# SECDONGL_001.net
KiCad netlist of a schematic drawn in EAGLE
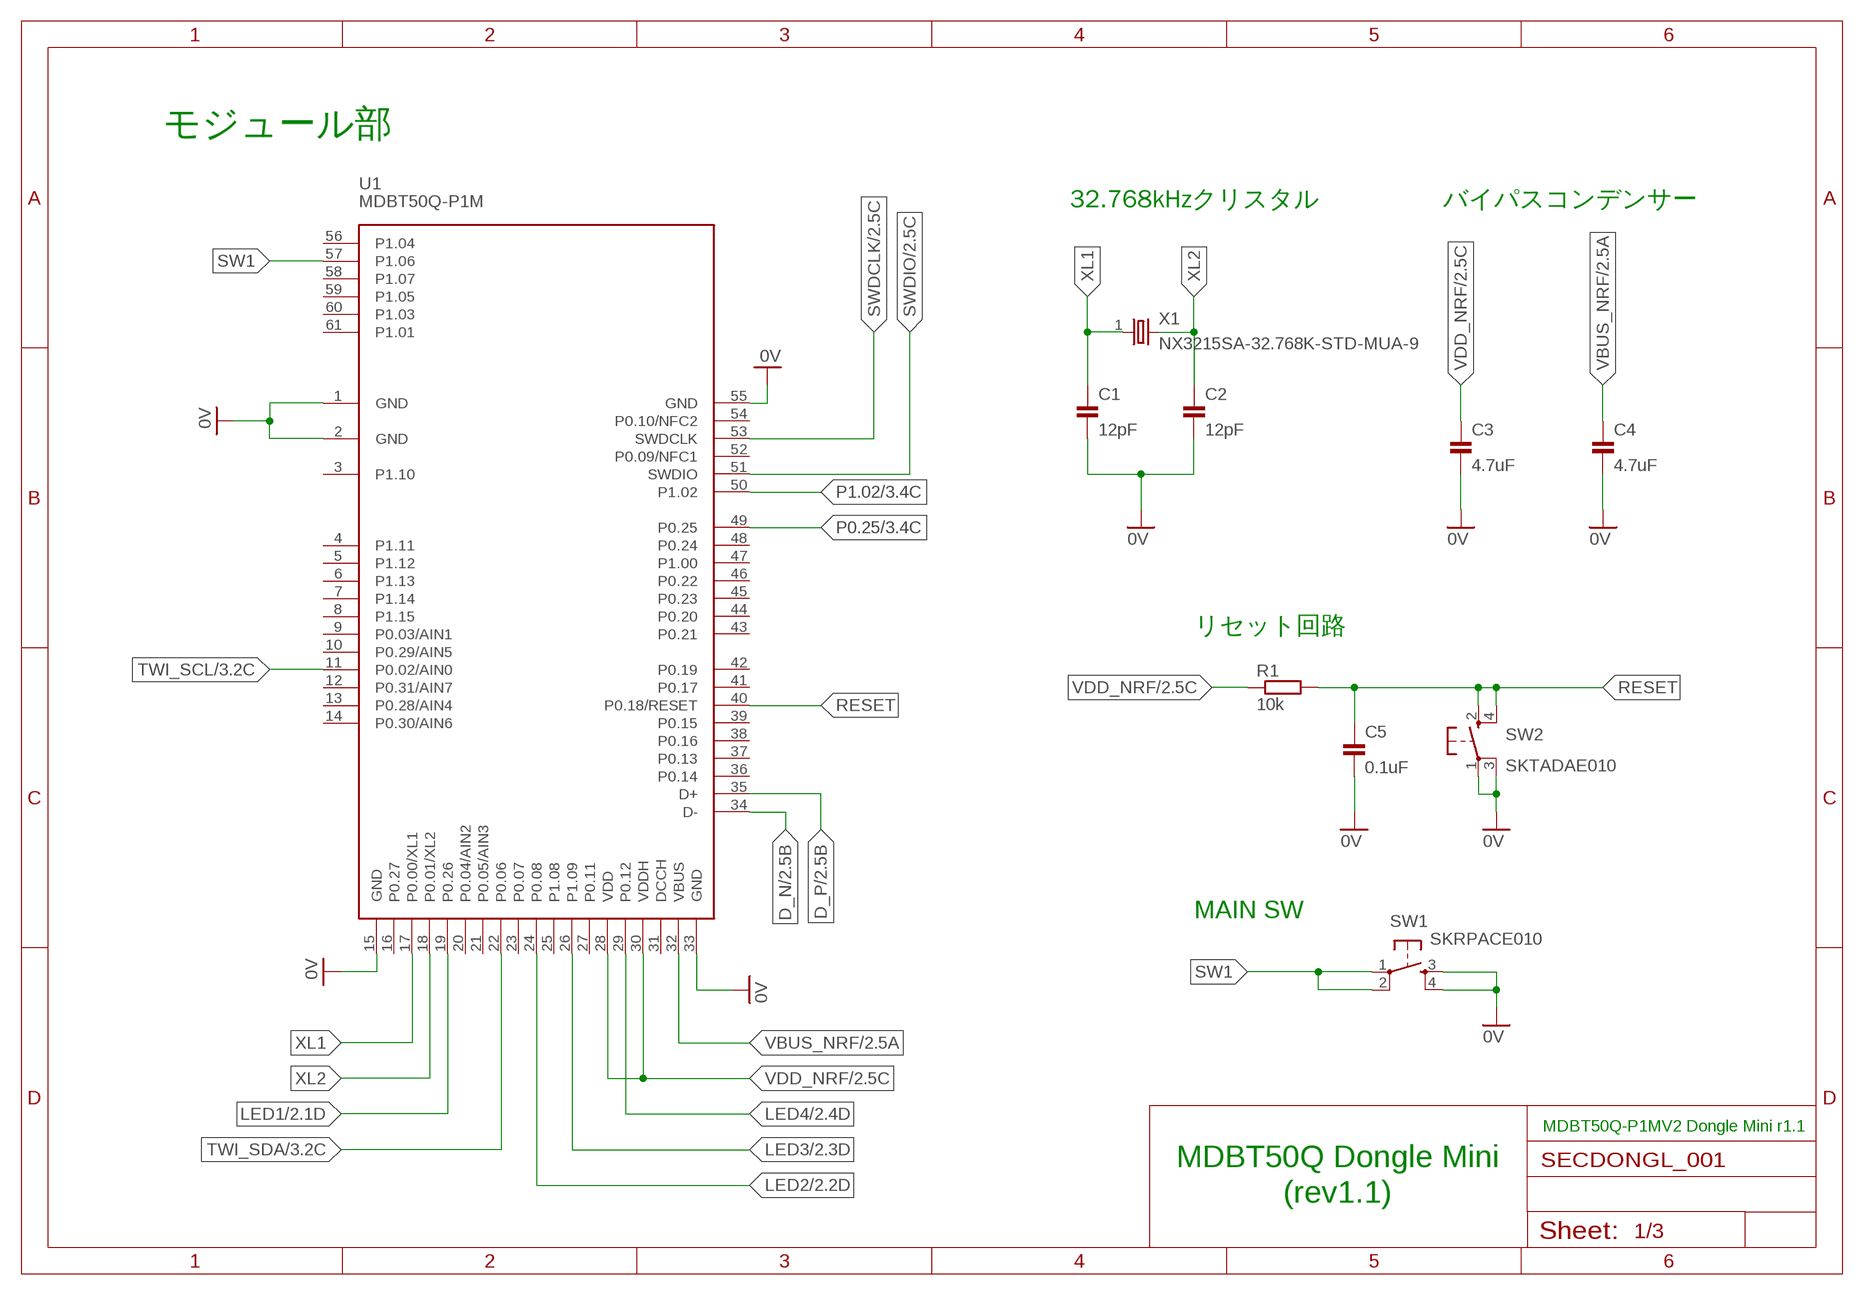
[diagram p0: schematic, sheet 1]
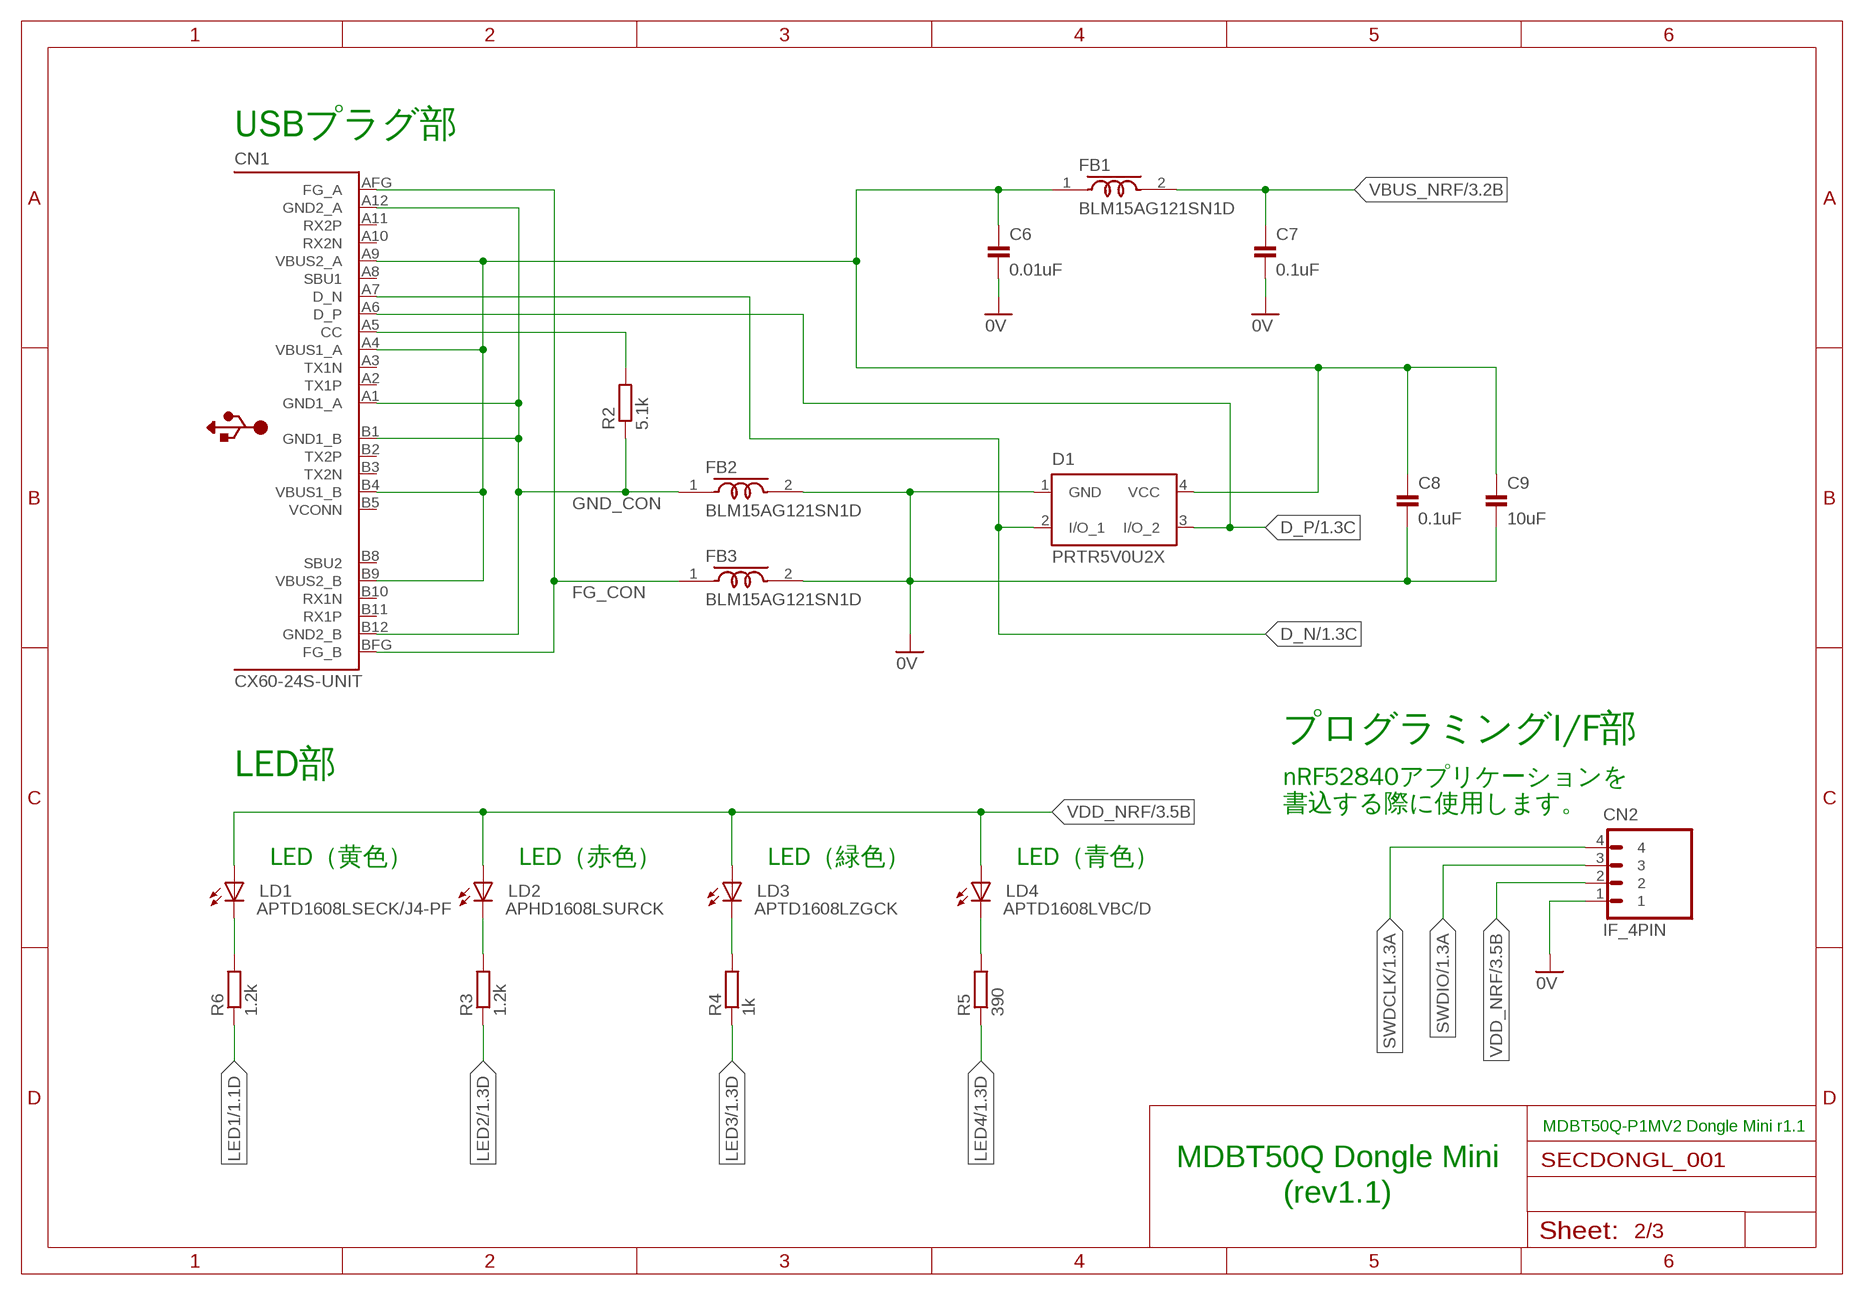
[diagram p1: schematic, sheet 2]
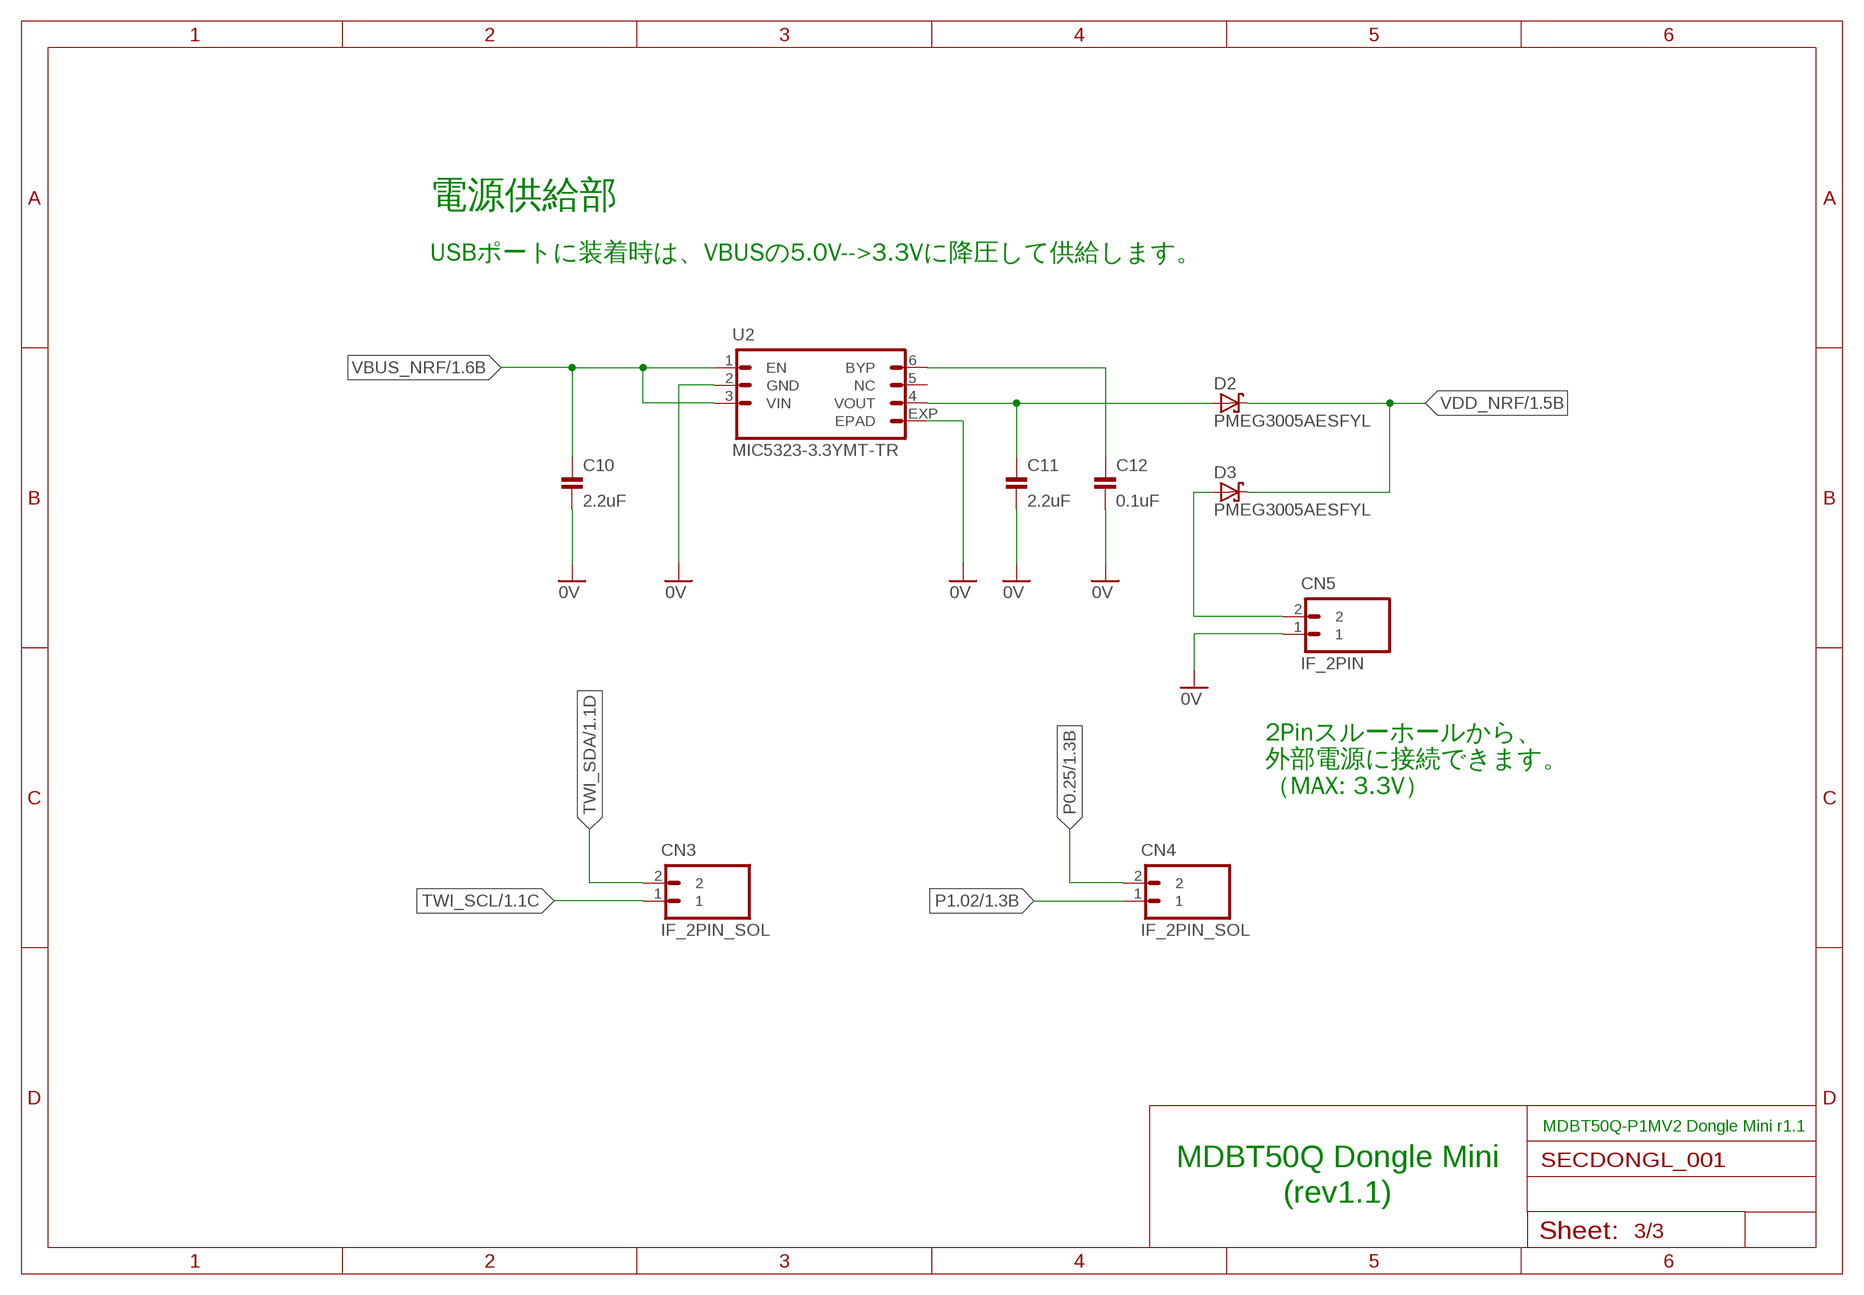
[diagram p2: schematic, sheet 3]

(export (version "E")
  (design (tool "Eeschema 10.0.6"))
  (components
    (comp (ref "C6")
      (value "0.01uF")
      (footprint "eagle-import:C0402K")
      (libsource (lib "eagle-import") (part "CAP_0402K"))
    )
    (comp (ref "C7")
      (value "0.1uF")
      (footprint "eagle-import:C0402K")
      (libsource (lib "eagle-import") (part "CAP_0402K"))
    )
    (comp (ref "C8")
      (value "0.1uF")
      (footprint "eagle-import:C0402K")
      (libsource (lib "eagle-import") (part "CAP_0402K"))
    )
    (comp (ref "C9")
      (value "10uF")
      (footprint "eagle-import:C0603K")
      (libsource (lib "eagle-import") (part "CAP_0603"))
    )
    (comp (ref "CN1")
      (value "CX60-24S-UNIT")
      (footprint "eagle-import:CX60-24S-UNIT")
      (libsource (lib "eagle-import") (part "CX60-24S-UNIT"))
    )
    (comp (ref "CN2")
      (value "IF_4PIN")
      (footprint "eagle-import:HEADER_4PIN")
      (libsource (lib "eagle-import") (part "IF_4PIN"))
    )
    (comp (ref "D1")
      (value "PRTR5V0U2X")
      (footprint "eagle-import:SOT143B")
      (libsource (lib "eagle-import") (part "PRTR5V0U2X"))
    )
    (comp (ref "FB1")
      (value "BLM15AG121SN1D")
      (footprint "eagle-import:C0402K")
      (libsource (lib "eagle-import") (part "BLM15AG121SN1D"))
    )
    (comp (ref "FB2")
      (value "BLM15AG121SN1D")
      (footprint "eagle-import:C0402K")
      (libsource (lib "eagle-import") (part "BLM15AG121SN1D"))
    )
    (comp (ref "FB3")
      (value "BLM15AG121SN1D")
      (footprint "eagle-import:C0402K")
      (libsource (lib "eagle-import") (part "BLM15AG121SN1D"))
    )
    (comp (ref "LD1")
      (value "APTD1608LSECK/J4-PF")
      (footprint "eagle-import:APTD1608")
      (libsource (lib "eagle-import") (part "APTD1608LSECK/J4-PF"))
    )
    (comp (ref "LD2")
      (value "APHD1608LSURCK")
      (footprint "eagle-import:APTD1608")
      (libsource (lib "eagle-import") (part "APHD1608LSURCK"))
    )
    (comp (ref "LD3")
      (value "APTD1608LZGCK")
      (footprint "eagle-import:APTD1608")
      (libsource (lib "eagle-import") (part "APTD1608LZGCK"))
    )
    (comp (ref "LD4")
      (value "APTD1608LVBC/D")
      (footprint "eagle-import:APTD1608")
      (libsource (lib "eagle-import") (part "APTD1608LVBC/D"))
    )
    (comp (ref "R2")
      (value "5.1k")
      (footprint "eagle-import:R0402")
      (libsource (lib "eagle-import") (part "RESISTOR_0402"))
    )
    (comp (ref "R3")
      (value "1.2k")
      (footprint "eagle-import:R0402")
      (libsource (lib "eagle-import") (part "RESISTOR_0402"))
    )
    (comp (ref "R4")
      (value "1k")
      (footprint "eagle-import:R0402")
      (libsource (lib "eagle-import") (part "RESISTOR_0402"))
    )
    (comp (ref "R5")
      (value "390")
      (footprint "eagle-import:R0402")
      (libsource (lib "eagle-import") (part "RESISTOR_0402"))
    )
    (comp (ref "R6")
      (value "1.2k")
      (footprint "eagle-import:R0402")
      (libsource (lib "eagle-import") (part "RESISTOR_0402"))
    )
    (comp (ref "C1")
      (value "12pF")
      (footprint "eagle-import:C0603K")
      (libsource (lib "eagle-import") (part "CAP_0603"))
    )
    (comp (ref "C2")
      (value "12pF")
      (footprint "eagle-import:C0603K")
      (libsource (lib "eagle-import") (part "CAP_0603"))
    )
    (comp (ref "C3")
      (value "4.7uF")
      (footprint "eagle-import:C0603K")
      (libsource (lib "eagle-import") (part "CAP_0603"))
    )
    (comp (ref "C4")
      (value "4.7uF")
      (footprint "eagle-import:C0603K")
      (libsource (lib "eagle-import") (part "CAP_0603"))
    )
    (comp (ref "C5")
      (value "0.1uF")
      (footprint "eagle-import:C0402K")
      (libsource (lib "eagle-import") (part "CAP_0402K"))
    )
    (comp (ref "R1")
      (value "10k")
      (footprint "eagle-import:R0402")
      (libsource (lib "eagle-import") (part "RESISTOR_0402"))
    )
    (comp (ref "SW1")
      (value "SKRPACE010")
      (footprint "eagle-import:SKRPACE010")
      (libsource (lib "eagle-import") (part "SKRPACE010"))
    )
    (comp (ref "SW2")
      (value "SKTADAE010")
      (footprint "eagle-import:SKTADAE010")
      (libsource (lib "eagle-import") (part "SKTADAE010"))
    )
    (comp (ref "U1")
      (value "MDBT50Q-P1M")
      (footprint "eagle-import:MDBT50Q-P1M")
      (libsource (lib "eagle-import") (part "MDBT50Q-P1M"))
    )
    (comp (ref "X1")
      (value "NX3215SA-32.768K-STD-MUA-9")
      (footprint "eagle-import:NX3215")
      (libsource (lib "eagle-import") (part "NX3215SA-32.768K-STD-MUA-9"))
    )
    (comp (ref "C10")
      (value "2.2uF")
      (footprint "eagle-import:C0603K")
      (libsource (lib "eagle-import") (part "CAP_0603"))
    )
    (comp (ref "C11")
      (value "2.2uF")
      (footprint "eagle-import:C0603K")
      (libsource (lib "eagle-import") (part "CAP_0603"))
    )
    (comp (ref "C12")
      (value "0.1uF")
      (footprint "eagle-import:C0402K")
      (libsource (lib "eagle-import") (part "CAP_0402K"))
    )
    (comp (ref "CN3")
      (value "IF_2PIN_SOL")
      (footprint "eagle-import:SOLPAD_2PIN")
      (libsource (lib "eagle-import") (part "IF_2PIN_SOL"))
    )
    (comp (ref "CN4")
      (value "IF_2PIN_SOL")
      (footprint "eagle-import:SOLPAD_2PIN")
      (libsource (lib "eagle-import") (part "IF_2PIN_SOL"))
    )
    (comp (ref "CN5")
      (value "IF_2PIN")
      (footprint "eagle-import:HEADER_2P")
      (libsource (lib "eagle-import") (part "IF_2PIN"))
    )
    (comp (ref "D2")
      (value "PMEG3005AESFYL")
      (footprint "eagle-import:SOD962-2")
      (libsource (lib "eagle-import") (part "PMEG3005AESFYL"))
    )
    (comp (ref "D3")
      (value "PMEG3005AESFYL")
      (footprint "eagle-import:SOD962-2")
      (libsource (lib "eagle-import") (part "PMEG3005AESFYL"))
    )
    (comp (ref "U2")
      (value "MIC5323-3.3YMT-TR")
      (footprint "eagle-import:6-VDFN(2X2)")
      (libsource (lib "eagle-import") (part "MIC5323-3.3YMT-TR"))
    )
  )
  (nets
    (net (code "1") (name "0V") (class "Default")
      (node (ref "C1") (pin "2") (pinfunction "2_2") (pintype "passive"))
      (node (ref "C10") (pin "2") (pinfunction "2_2") (pintype "passive"))
      (node (ref "C11") (pin "2") (pinfunction "2_2") (pintype "passive"))
      (node (ref "C12") (pin "2") (pinfunction "2_2") (pintype "passive"))
      (node (ref "C2") (pin "2") (pinfunction "2_2") (pintype "passive"))
      (node (ref "C3") (pin "2") (pinfunction "2_2") (pintype "passive"))
      (node (ref "C4") (pin "2") (pinfunction "2_2") (pintype "passive"))
      (node (ref "C5") (pin "2") (pinfunction "2_2") (pintype "passive"))
      (node (ref "C6") (pin "2") (pinfunction "2_2") (pintype "passive"))
      (node (ref "C7") (pin "2") (pinfunction "2_2") (pintype "passive"))
      (node (ref "C8") (pin "2") (pinfunction "2_2") (pintype "passive"))
      (node (ref "C9") (pin "2") (pinfunction "2_2") (pintype "passive"))
      (node (ref "CN2") (pin "1") (pinfunction "1_1") (pintype "passive"))
      (node (ref "CN5") (pin "1") (pinfunction "1_1") (pintype "passive"))
      (node (ref "D1") (pin "1") (pinfunction "GND_1") (pintype "passive"))
      (node (ref "FB2") (pin "2") (pinfunction "2_2") (pintype "passive"))
      (node (ref "FB3") (pin "2") (pinfunction "2_2") (pintype "passive"))
      (node (ref "SW1") (pin "3") (pinfunction "S_3") (pintype "passive"))
      (node (ref "SW1") (pin "4") (pinfunction "S1_4") (pintype "passive"))
      (node (ref "SW2") (pin "1") (pinfunction "P_1") (pintype "passive"))
      (node (ref "SW2") (pin "3") (pinfunction "P1_3") (pintype "passive"))
      (node (ref "U1") (pin "1") (pinfunction "GND_1") (pintype "bidirectional"))
      (node (ref "U1") (pin "15") (pinfunction "GND_15") (pintype "bidirectional"))
      (node (ref "U1") (pin "2") (pinfunction "GND_2") (pintype "bidirectional"))
      (node (ref "U1") (pin "33") (pinfunction "GND_33") (pintype "bidirectional"))
      (node (ref "U1") (pin "55") (pinfunction "GND_55") (pintype "bidirectional"))
      (node (ref "U2") (pin "2") (pinfunction "GND_2") (pintype "passive"))
      (node (ref "U2") (pin "EXP") (pinfunction "EPAD_EXP") (pintype "passive"))
    )
    (net (code "2") (name "D_N") (class "Default")
      (node (ref "CN1") (pin "A7") (pinfunction "D_N_A7") (pintype "bidirectional"))
      (node (ref "D1") (pin "2") (pinfunction "I/O_1_2") (pintype "bidirectional"))
      (node (ref "U1") (pin "34") (pinfunction "D-_34") (pintype "bidirectional"))
    )
    (net (code "3") (name "D_P") (class "Default")
      (node (ref "CN1") (pin "A6") (pinfunction "D_P_A6") (pintype "bidirectional"))
      (node (ref "D1") (pin "3") (pinfunction "I/O_2_3") (pintype "bidirectional"))
      (node (ref "U1") (pin "35") (pinfunction "D+_35") (pintype "bidirectional"))
    )
    (net (code "4") (name "FG_CON") (class "Default")
      (node (ref "CN1") (pin "AFG") (pinfunction "FG_A_AFG") (pintype "passive"))
      (node (ref "CN1") (pin "BFG") (pinfunction "FG_B_BFG") (pintype "passive"))
      (node (ref "FB3") (pin "1") (pinfunction "1_1") (pintype "passive"))
    )
    (net (code "5") (name "GND_CON") (class "Default")
      (node (ref "CN1") (pin "A1") (pinfunction "GND1_A_A1") (pintype "passive"))
      (node (ref "CN1") (pin "A12") (pinfunction "GND2_A_A12") (pintype "bidirectional"))
      (node (ref "CN1") (pin "B1") (pinfunction "GND1_B_B1") (pintype "passive"))
      (node (ref "CN1") (pin "B12") (pinfunction "GND2_B_B12") (pintype "passive"))
      (node (ref "FB2") (pin "1") (pinfunction "1_1") (pintype "passive"))
      (node (ref "R2") (pin "1") (pinfunction "1_1") (pintype "passive"))
    )
    (net (code "6") (name "LED1") (class "Default")
      (node (ref "R6") (pin "1") (pinfunction "1_1") (pintype "passive"))
      (node (ref "U1") (pin "19") (pinfunction "P0.26_19") (pintype "bidirectional"))
    )
    (net (code "7") (name "LED2") (class "Default")
      (node (ref "R3") (pin "1") (pinfunction "1_1") (pintype "passive"))
      (node (ref "U1") (pin "24") (pinfunction "P0.08_24") (pintype "bidirectional"))
    )
    (net (code "8") (name "LED3") (class "Default")
      (node (ref "R4") (pin "1") (pinfunction "1_1") (pintype "passive"))
      (node (ref "U1") (pin "26") (pinfunction "P1.09_26") (pintype "bidirectional"))
    )
    (net (code "9") (name "LED4") (class "Default")
      (node (ref "R5") (pin "1") (pinfunction "1_1") (pintype "passive"))
      (node (ref "U1") (pin "29") (pinfunction "P0.12_29") (pintype "bidirectional"))
    )
    (net (code "10") (name "Net-(CN1-CC)") (class "Default")
      (node (ref "CN1") (pin "A5") (pinfunction "CC_A5") (pintype "passive"))
      (node (ref "R2") (pin "2") (pinfunction "2_2") (pintype "passive"))
    )
    (net (code "11") (name "Net-(CN1-VBUS1_A)") (class "Default")
      (node (ref "C6") (pin "1") (pinfunction "1_1") (pintype "passive"))
      (node (ref "C8") (pin "1") (pinfunction "1_1") (pintype "passive"))
      (node (ref "C9") (pin "1") (pinfunction "1_1") (pintype "passive"))
      (node (ref "CN1") (pin "A4") (pinfunction "VBUS1_A_A4") (pintype "passive"))
      (node (ref "CN1") (pin "A9") (pinfunction "VBUS2_A_A9") (pintype "passive"))
      (node (ref "CN1") (pin "B4") (pinfunction "VBUS1_B_B4") (pintype "passive"))
      (node (ref "CN1") (pin "B9") (pinfunction "VBUS2_B_B9") (pintype "passive"))
      (node (ref "D1") (pin "4") (pinfunction "VCC_4") (pintype "passive"))
      (node (ref "FB1") (pin "1") (pinfunction "1_1") (pintype "passive"))
    )
    (net (code "12") (name "Net-(CN5-Pad2)") (class "Default")
      (node (ref "CN5") (pin "2") (pinfunction "2_2") (pintype "passive"))
      (node (ref "D3") (pin "A") (pinfunction "A_A") (pintype "passive"))
    )
    (net (code "13") (name "Net-(LD1-PadC)") (class "Default")
      (node (ref "LD1") (pin "C") (pinfunction "C_C") (pintype "passive"))
      (node (ref "R6") (pin "2") (pinfunction "2_2") (pintype "passive"))
    )
    (net (code "14") (name "Net-(LD2-PadC)") (class "Default")
      (node (ref "LD2") (pin "C") (pinfunction "C_C") (pintype "passive"))
      (node (ref "R3") (pin "2") (pinfunction "2_2") (pintype "passive"))
    )
    (net (code "15") (name "Net-(LD3-PadC)") (class "Default")
      (node (ref "LD3") (pin "C") (pinfunction "C_C") (pintype "passive"))
      (node (ref "R4") (pin "2") (pinfunction "2_2") (pintype "passive"))
    )
    (net (code "16") (name "Net-(LD4-PadC)") (class "Default")
      (node (ref "LD4") (pin "C") (pinfunction "C_C") (pintype "passive"))
      (node (ref "R5") (pin "2") (pinfunction "2_2") (pintype "passive"))
    )
    (net (code "17") (name "Net-(U2-BYP)") (class "Default")
      (node (ref "C12") (pin "1") (pinfunction "1_1") (pintype "passive"))
      (node (ref "U2") (pin "6") (pinfunction "BYP_6") (pintype "passive"))
    )
    (net (code "18") (name "Net-(U2-VOUT)") (class "Default")
      (node (ref "C11") (pin "1") (pinfunction "1_1") (pintype "passive"))
      (node (ref "D2") (pin "A") (pinfunction "A_A") (pintype "passive"))
      (node (ref "U2") (pin "4") (pinfunction "VOUT_4") (pintype "passive"))
    )
    (net (code "19") (name "P0.25") (class "Default")
      (node (ref "CN4") (pin "2") (pinfunction "2_2") (pintype "passive"))
      (node (ref "U1") (pin "49") (pinfunction "P0.25_49") (pintype "bidirectional"))
    )
    (net (code "20") (name "P1.02") (class "Default")
      (node (ref "CN4") (pin "1") (pinfunction "1_1") (pintype "passive"))
      (node (ref "U1") (pin "50") (pinfunction "P1.02_50") (pintype "bidirectional"))
    )
    (net (code "21") (name "RESET") (class "Default")
      (node (ref "C5") (pin "1") (pinfunction "1_1") (pintype "passive"))
      (node (ref "R1") (pin "2") (pinfunction "2_2") (pintype "passive"))
      (node (ref "SW2") (pin "2") (pinfunction "S_2") (pintype "passive"))
      (node (ref "SW2") (pin "4") (pinfunction "S1_4") (pintype "passive"))
      (node (ref "U1") (pin "40") (pinfunction "P0.18/RESET_40") (pintype "bidirectional"))
    )
    (net (code "22") (name "SW1") (class "Default")
      (node (ref "SW1") (pin "1") (pinfunction "P_1") (pintype "passive"))
      (node (ref "SW1") (pin "2") (pinfunction "P1_2") (pintype "passive"))
      (node (ref "U1") (pin "57") (pinfunction "P1.06_57") (pintype "bidirectional"))
    )
    (net (code "23") (name "SWDCLK") (class "Default")
      (node (ref "CN2") (pin "4") (pinfunction "4_4") (pintype "passive"))
      (node (ref "U1") (pin "53") (pinfunction "SWDCLK_53") (pintype "bidirectional"))
    )
    (net (code "24") (name "SWDIO") (class "Default")
      (node (ref "CN2") (pin "3") (pinfunction "3_3") (pintype "passive"))
      (node (ref "U1") (pin "51") (pinfunction "SWDIO_51") (pintype "bidirectional"))
    )
    (net (code "25") (name "TWI_SCL") (class "Default")
      (node (ref "CN3") (pin "1") (pinfunction "1_1") (pintype "passive"))
      (node (ref "U1") (pin "11") (pinfunction "P0.02/AIN0_11") (pintype "bidirectional"))
    )
    (net (code "26") (name "TWI_SDA") (class "Default")
      (node (ref "CN3") (pin "2") (pinfunction "2_2") (pintype "passive"))
      (node (ref "U1") (pin "22") (pinfunction "P0.06_22") (pintype "bidirectional"))
    )
    (net (code "27") (name "VBUS_NRF") (class "Default")
      (node (ref "C10") (pin "1") (pinfunction "1_1") (pintype "passive"))
      (node (ref "C4") (pin "1") (pinfunction "1_1") (pintype "passive"))
      (node (ref "C7") (pin "1") (pinfunction "1_1") (pintype "passive"))
      (node (ref "FB1") (pin "2") (pinfunction "2_2") (pintype "passive"))
      (node (ref "U1") (pin "32") (pinfunction "VBUS_32") (pintype "bidirectional"))
      (node (ref "U2") (pin "1") (pinfunction "EN_1") (pintype "bidirectional"))
      (node (ref "U2") (pin "3") (pinfunction "VIN_3") (pintype "passive"))
    )
    (net (code "28") (name "VDD_NRF") (class "Default")
      (node (ref "C3") (pin "1") (pinfunction "1_1") (pintype "passive"))
      (node (ref "CN2") (pin "2") (pinfunction "2_2") (pintype "passive"))
      (node (ref "D2") (pin "C") (pinfunction "C_C") (pintype "passive"))
      (node (ref "D3") (pin "C") (pinfunction "C_C") (pintype "passive"))
      (node (ref "LD1") (pin "A") (pinfunction "A_A") (pintype "passive"))
      (node (ref "LD2") (pin "A") (pinfunction "A_A") (pintype "passive"))
      (node (ref "LD3") (pin "A") (pinfunction "A_A") (pintype "passive"))
      (node (ref "LD4") (pin "A") (pinfunction "A_A") (pintype "passive"))
      (node (ref "R1") (pin "1") (pinfunction "1_1") (pintype "passive"))
      (node (ref "U1") (pin "28") (pinfunction "VDD_28") (pintype "bidirectional"))
      (node (ref "U1") (pin "30") (pinfunction "VDDH_30") (pintype "bidirectional"))
    )
    (net (code "29") (name "XL1") (class "Default")
      (node (ref "C1") (pin "1") (pinfunction "1_1") (pintype "passive"))
      (node (ref "U1") (pin "17") (pinfunction "P0.00/XL1_17") (pintype "bidirectional"))
      (node (ref "X1") (pin "1") (pinfunction "1_1") (pintype "passive"))
    )
    (net (code "30") (name "XL2") (class "Default")
      (node (ref "C2") (pin "1") (pinfunction "1_1") (pintype "passive"))
      (node (ref "U1") (pin "18") (pinfunction "P0.01/XL2_18") (pintype "bidirectional"))
      (node (ref "X1") (pin "2") (pinfunction "2_2") (pintype "passive"))
    )
    (net (code "31") (name "unconnected-(CN1-RX1N-PadB10)") (class "Default")
      (node (ref "CN1") (pin "B10") (pinfunction "RX1N_B10") (pintype "bidirectional"))
    )
    (net (code "32") (name "unconnected-(CN1-RX1P-PadB11)") (class "Default")
      (node (ref "CN1") (pin "B11") (pinfunction "RX1P_B11") (pintype "bidirectional"))
    )
    (net (code "33") (name "unconnected-(CN1-RX2N-PadA10)") (class "Default")
      (node (ref "CN1") (pin "A10") (pinfunction "RX2N_A10") (pintype "passive"))
    )
    (net (code "34") (name "unconnected-(CN1-RX2P-PadA11)") (class "Default")
      (node (ref "CN1") (pin "A11") (pinfunction "RX2P_A11") (pintype "bidirectional"))
    )
    (net (code "35") (name "unconnected-(CN1-SBU1-PadA8)") (class "Default")
      (node (ref "CN1") (pin "A8") (pinfunction "SBU1_A8") (pintype "passive"))
    )
    (net (code "36") (name "unconnected-(CN1-SBU2-PadB8)") (class "Default")
      (node (ref "CN1") (pin "B8") (pinfunction "SBU2_B8") (pintype "passive"))
    )
    (net (code "37") (name "unconnected-(CN1-TX1N-PadA3)") (class "Default")
      (node (ref "CN1") (pin "A3") (pinfunction "TX1N_A3") (pintype "bidirectional"))
    )
    (net (code "38") (name "unconnected-(CN1-TX1P-PadA2)") (class "Default")
      (node (ref "CN1") (pin "A2") (pinfunction "TX1P_A2") (pintype "bidirectional"))
    )
    (net (code "39") (name "unconnected-(CN1-TX2N-PadB3)") (class "Default")
      (node (ref "CN1") (pin "B3") (pinfunction "TX2N_B3") (pintype "bidirectional"))
    )
    (net (code "40") (name "unconnected-(CN1-TX2P-PadB2)") (class "Default")
      (node (ref "CN1") (pin "B2") (pinfunction "TX2P_B2") (pintype "bidirectional"))
    )
    (net (code "41") (name "unconnected-(CN1-VCONN-PadB5)") (class "Default")
      (node (ref "CN1") (pin "B5") (pinfunction "VCONN_B5") (pintype "passive"))
    )
    (net (code "42") (name "unconnected-(U1-DCCH-Pad31)") (class "Default")
      (node (ref "U1") (pin "31") (pinfunction "DCCH_31") (pintype "bidirectional"))
    )
    (net (code "43") (name "unconnected-(U1-P0.03{slash}AIN1-Pad9)") (class "Default")
      (node (ref "U1") (pin "9") (pinfunction "P0.03/AIN1_9") (pintype "bidirectional"))
    )
    (net (code "44") (name "unconnected-(U1-P0.04{slash}AIN2-Pad20)") (class "Default")
      (node (ref "U1") (pin "20") (pinfunction "P0.04/AIN2_20") (pintype "bidirectional"))
    )
    (net (code "45") (name "unconnected-(U1-P0.05{slash}AIN3-Pad21)") (class "Default")
      (node (ref "U1") (pin "21") (pinfunction "P0.05/AIN3_21") (pintype "bidirectional"))
    )
    (net (code "46") (name "unconnected-(U1-P0.07-Pad23)") (class "Default")
      (node (ref "U1") (pin "23") (pinfunction "P0.07_23") (pintype "bidirectional"))
    )
    (net (code "47") (name "unconnected-(U1-P0.09{slash}NFC1-Pad52)") (class "Default")
      (node (ref "U1") (pin "52") (pinfunction "P0.09/NFC1_52") (pintype "bidirectional"))
    )
    (net (code "48") (name "unconnected-(U1-P0.10{slash}NFC2-Pad54)") (class "Default")
      (node (ref "U1") (pin "54") (pinfunction "P0.10/NFC2_54") (pintype "bidirectional"))
    )
    (net (code "49") (name "unconnected-(U1-P0.11-Pad27)") (class "Default")
      (node (ref "U1") (pin "27") (pinfunction "P0.11_27") (pintype "bidirectional"))
    )
    (net (code "50") (name "unconnected-(U1-P0.13-Pad37)") (class "Default")
      (node (ref "U1") (pin "37") (pinfunction "P0.13_37") (pintype "bidirectional"))
    )
    (net (code "51") (name "unconnected-(U1-P0.14-Pad36)") (class "Default")
      (node (ref "U1") (pin "36") (pinfunction "P0.14_36") (pintype "bidirectional"))
    )
    (net (code "52") (name "unconnected-(U1-P0.15-Pad39)") (class "Default")
      (node (ref "U1") (pin "39") (pinfunction "P0.15_39") (pintype "bidirectional"))
    )
    (net (code "53") (name "unconnected-(U1-P0.16-Pad38)") (class "Default")
      (node (ref "U1") (pin "38") (pinfunction "P0.16_38") (pintype "bidirectional"))
    )
    (net (code "54") (name "unconnected-(U1-P0.17-Pad41)") (class "Default")
      (node (ref "U1") (pin "41") (pinfunction "P0.17_41") (pintype "bidirectional"))
    )
    (net (code "55") (name "unconnected-(U1-P0.19-Pad42)") (class "Default")
      (node (ref "U1") (pin "42") (pinfunction "P0.19_42") (pintype "bidirectional"))
    )
    (net (code "56") (name "unconnected-(U1-P0.20-Pad44)") (class "Default")
      (node (ref "U1") (pin "44") (pinfunction "P0.20_44") (pintype "bidirectional"))
    )
    (net (code "57") (name "unconnected-(U1-P0.21-Pad43)") (class "Default")
      (node (ref "U1") (pin "43") (pinfunction "P0.21_43") (pintype "bidirectional"))
    )
    (net (code "58") (name "unconnected-(U1-P0.22-Pad46)") (class "Default")
      (node (ref "U1") (pin "46") (pinfunction "P0.22_46") (pintype "bidirectional"))
    )
    (net (code "59") (name "unconnected-(U1-P0.23-Pad45)") (class "Default")
      (node (ref "U1") (pin "45") (pinfunction "P0.23_45") (pintype "bidirectional"))
    )
    (net (code "60") (name "unconnected-(U1-P0.24-Pad48)") (class "Default")
      (node (ref "U1") (pin "48") (pinfunction "P0.24_48") (pintype "bidirectional"))
    )
    (net (code "61") (name "unconnected-(U1-P0.27-Pad16)") (class "Default")
      (node (ref "U1") (pin "16") (pinfunction "P0.27_16") (pintype "bidirectional"))
    )
    (net (code "62") (name "unconnected-(U1-P0.28{slash}AIN4-Pad13)") (class "Default")
      (node (ref "U1") (pin "13") (pinfunction "P0.28/AIN4_13") (pintype "bidirectional"))
    )
    (net (code "63") (name "unconnected-(U1-P0.29{slash}AIN5-Pad10)") (class "Default")
      (node (ref "U1") (pin "10") (pinfunction "P0.29/AIN5_10") (pintype "bidirectional"))
    )
    (net (code "64") (name "unconnected-(U1-P0.30{slash}AIN6-Pad14)") (class "Default")
      (node (ref "U1") (pin "14") (pinfunction "P0.30/AIN6_14") (pintype "bidirectional"))
    )
    (net (code "65") (name "unconnected-(U1-P0.31{slash}AIN7-Pad12)") (class "Default")
      (node (ref "U1") (pin "12") (pinfunction "P0.31/AIN7_12") (pintype "bidirectional"))
    )
    (net (code "66") (name "unconnected-(U1-P1.00-Pad47)") (class "Default")
      (node (ref "U1") (pin "47") (pinfunction "P1.00_47") (pintype "bidirectional"))
    )
    (net (code "67") (name "unconnected-(U1-P1.01-Pad61)") (class "Default")
      (node (ref "U1") (pin "61") (pinfunction "P1.01_61") (pintype "bidirectional"))
    )
    (net (code "68") (name "unconnected-(U1-P1.03-Pad60)") (class "Default")
      (node (ref "U1") (pin "60") (pinfunction "P1.03_60") (pintype "bidirectional"))
    )
    (net (code "69") (name "unconnected-(U1-P1.04-Pad56)") (class "Default")
      (node (ref "U1") (pin "56") (pinfunction "P1.04_56") (pintype "bidirectional"))
    )
    (net (code "70") (name "unconnected-(U1-P1.05-Pad59)") (class "Default")
      (node (ref "U1") (pin "59") (pinfunction "P1.05_59") (pintype "bidirectional"))
    )
    (net (code "71") (name "unconnected-(U1-P1.07-Pad58)") (class "Default")
      (node (ref "U1") (pin "58") (pinfunction "P1.07_58") (pintype "bidirectional"))
    )
    (net (code "72") (name "unconnected-(U1-P1.08-Pad25)") (class "Default")
      (node (ref "U1") (pin "25") (pinfunction "P1.08_25") (pintype "bidirectional"))
    )
    (net (code "73") (name "unconnected-(U1-P1.10-Pad3)") (class "Default")
      (node (ref "U1") (pin "3") (pinfunction "P1.10_3") (pintype "bidirectional"))
    )
    (net (code "74") (name "unconnected-(U1-P1.11-Pad4)") (class "Default")
      (node (ref "U1") (pin "4") (pinfunction "P1.11_4") (pintype "bidirectional"))
    )
    (net (code "75") (name "unconnected-(U1-P1.12-Pad5)") (class "Default")
      (node (ref "U1") (pin "5") (pinfunction "P1.12_5") (pintype "bidirectional"))
    )
    (net (code "76") (name "unconnected-(U1-P1.13-Pad6)") (class "Default")
      (node (ref "U1") (pin "6") (pinfunction "P1.13_6") (pintype "bidirectional"))
    )
    (net (code "77") (name "unconnected-(U1-P1.14-Pad7)") (class "Default")
      (node (ref "U1") (pin "7") (pinfunction "P1.14_7") (pintype "bidirectional"))
    )
    (net (code "78") (name "unconnected-(U1-P1.15-Pad8)") (class "Default")
      (node (ref "U1") (pin "8") (pinfunction "P1.15_8") (pintype "bidirectional"))
    )
    (net (code "79") (name "unconnected-(U2-NC-Pad5)") (class "Default")
      (node (ref "U2") (pin "5") (pinfunction "NC_5") (pintype "passive"))
    )
  )
)
